# Filters_PWM1kHz.net
KiCad netlist of a schematic drawn in Altium Designer
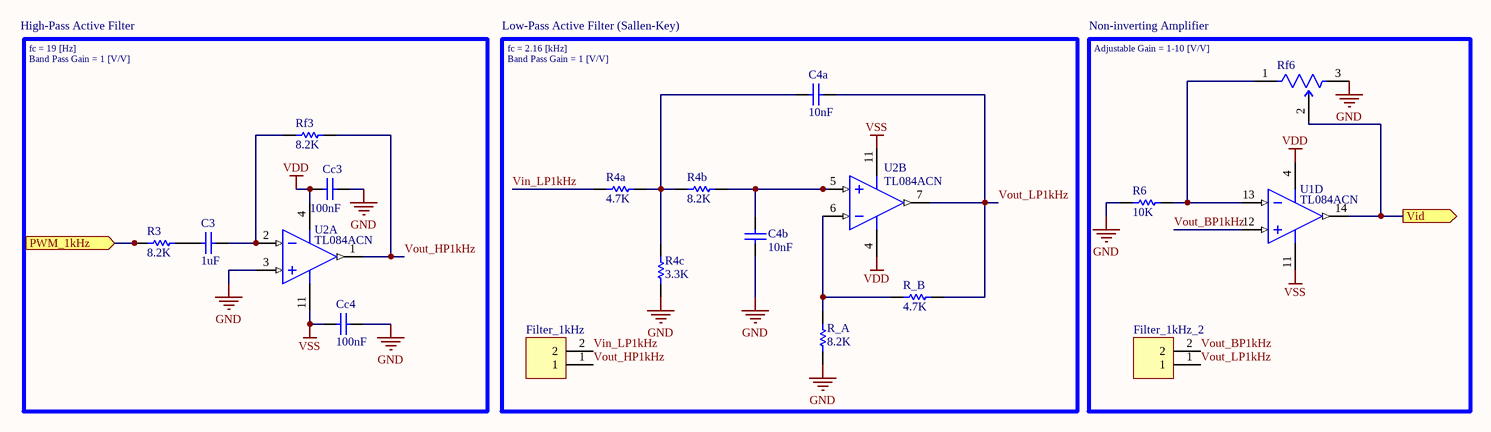
[diagram p0: Filters_PWM1kHz.SchDoc]

(export (version "E")
  (design (tool "Eeschema 10.0.6"))
  (components
    (comp (ref "C3")
      (value "1uF")
      (footprint "condensateur 0.1uf 100mil")
      (description "Capacitor")
      (fields (field (name "Comment") "Cap") (field (name "PUBLISHER") "Altium Limited"))
      (libsource (lib "signal-generator") (part "Cap"))
    )
    (comp (ref "C4a")
      (value "10nF")
      (footprint "condensateur 0.1uf 100mil")
      (description "Capacitor")
      (fields (field (name "Comment") "Cap") (field (name "PUBLISHER") "Altium Limited"))
      (libsource (lib "signal-generator") (part "Cap"))
    )
    (comp (ref "C4b")
      (value "10nF")
      (footprint "condensateur 0.1uf 100mil")
      (description "Capacitor")
      (fields (field (name "Comment") "Cap") (field (name "PUBLISHER") "Altium Limited"))
      (libsource (lib "signal-generator") (part "Cap"))
    )
    (comp (ref "Cc3")
      (value "100nF")
      (footprint "condensateur 0.1uf 100mil")
      (description "Capacitor")
      (fields (field (name "Comment") "Cap") (field (name "PUBLISHER") "Altium Limited"))
      (libsource (lib "signal-generator") (part "Cap"))
    )
    (comp (ref "Cc4")
      (value "100nF")
      (footprint "condensateur 0.1uf 100mil")
      (description "Capacitor")
      (fields (field (name "Comment") "Cap") (field (name "PUBLISHER") "Altium Limited"))
      (libsource (lib "signal-generator") (part "Cap"))
    )
    (comp (ref "Filter_1kHz")
      (value "Jumper")
      (footprint "Header 2P 100mil")
      (description "CONN HEADER VERT 3POS 2.54MM")
      (fields (field (name "PUBLISHER") "Altium Limited"))
      (libsource (lib "PCB_Alimentation_équipe1") (part "header 2 pin_UL"))
    )
    (comp (ref "Filter_1kHz_2")
      (value "Jumper")
      (footprint "Header 2P 100mil")
      (description "CONN HEADER VERT 3POS 2.54MM")
      (fields (field (name "PUBLISHER") "Altium Limited"))
      (libsource (lib "PCB_Alimentation_équipe1") (part "header 2 pin_UL"))
    )
    (comp (ref "R3")
      (value "8.2K")
      (footprint "Resistor_Axial 0.4")
      (description "Resistor")
      (fields (field (name "Comment") "Res1") (field (name "PUBLISHER") "Altium Limited"))
      (libsource (lib "signal-generator") (part "Res1"))
    )
    (comp (ref "R4a")
      (value "4.7K")
      (footprint "Resistor_Axial 0.4")
      (description "Resistor")
      (fields (field (name "Comment") "Res1") (field (name "PUBLISHER") "Altium Limited"))
      (libsource (lib "signal-generator") (part "Res1"))
    )
    (comp (ref "R4b")
      (value "8.2K")
      (footprint "Resistor_Axial 0.4")
      (description "Resistor")
      (fields (field (name "Comment") "Res1") (field (name "PUBLISHER") "Altium Limited"))
      (libsource (lib "signal-generator") (part "Res1"))
    )
    (comp (ref "R4c")
      (value "3.3K")
      (footprint "Resistor_Axial 0.4")
      (description "Resistor")
      (fields (field (name "Comment") "Res1") (field (name "PUBLISHER") "Altium Limited"))
      (libsource (lib "signal-generator") (part "Res1"))
    )
    (comp (ref "R6")
      (value "10K")
      (footprint "Resistor_Axial 0.4")
      (description "Resistor")
      (fields (field (name "Comment") "Res1") (field (name "PUBLISHER") "Altium Limited"))
      (libsource (lib "signal-generator") (part "Res1"))
    )
    (comp (ref "Rf3")
      (value "8.2K")
      (footprint "Resistor_Axial 0.4")
      (description "Resistor")
      (fields (field (name "Comment") "Res1") (field (name "PUBLISHER") "Altium Limited"))
      (libsource (lib "signal-generator") (part "Res1"))
    )
    (comp (ref "Rf6")
      (value "67WR100KLF")
      (footprint "FP-67W-MFG")
      (description "TRIMMER 100K OHM 0.5W PC PIN TOP")
      (fields (field (name "TOLERANCE") "10%"))
      (libsource (lib "Altium Content Vault") (part "a77ee20e32664c43a3a1dd5392b6021"))
    )
    (comp (ref "R_A")
      (value "8.2K")
      (footprint "Resistor_Axial 0.4")
      (description "Resistor")
      (fields (field (name "Comment") "Res1") (field (name "PUBLISHER") "Altium Limited"))
      (libsource (lib "signal-generator") (part "Res1"))
    )
    (comp (ref "R_B")
      (value "4.7K")
      (footprint "Resistor_Axial 0.4")
      (description "Resistor")
      (fields (field (name "Comment") "Res1") (field (name "PUBLISHER") "Altium Limited"))
      (libsource (lib "signal-generator") (part "Res1"))
    )
    (comp (ref "U1")
      (value "TL084ACN")
      (footprint "N0014A")
      (description "JFET-Input Operational Amplifier, 7 to 36 V, 0 to 70 degC, 14-pin DIP (N14), Pb-Free (RoHS)")
      (fields (field (name "MANUFACTURER") "Texas Instruments"))
      (libsource (lib "Altium Content Vault") (part "TI-TLXX4X_MC3403-X14"))
    )
    (comp (ref "U2")
      (value "TL084ACN")
      (footprint "N0014A")
      (description "JFET-Input Operational Amplifier, 7 to 36 V, 0 to 70 degC, 14-pin DIP (N14), Pb-Free (RoHS)")
      (fields (field (name "MANUFACTURER") "Texas Instruments"))
      (libsource (lib "Altium Content Vault") (part "TI-TLXX4X_MC3403-X14"))
    )
  )
  (nets
    (net (code "1") (name "/PWM_1kHz") (class "Default")
      (node (ref "R3") (pin "1") (pinfunction "1_1") (pintype "passive"))
    )
    (net (code "2") (name "/Vid") (class "Default")
      (node (ref "Rf6") (pin "2") (pinfunction "2_2") (pintype "passive"))
      (node (ref "U1") (pin "14") (pinfunction "OUT4_14") (pintype "output"))
    )
    (net (code "3") (name "/Vin_LP1kHz") (class "Default")
      (node (ref "Filter_1kHz") (pin "2") (pinfunction "2_2") (pintype "passive"))
      (node (ref "R4a") (pin "1") (pinfunction "1_1") (pintype "passive"))
    )
    (net (code "4") (name "/Vout_BP1kHz") (class "Default")
      (node (ref "Filter_1kHz_2") (pin "2") (pinfunction "2_2") (pintype "passive"))
      (node (ref "U1") (pin "12") (pinfunction "IN4+_12") (pintype "input"))
    )
    (net (code "5") (name "/Vout_HP1kHz") (class "Default")
      (node (ref "Filter_1kHz") (pin "1") (pinfunction "1_1") (pintype "passive"))
      (node (ref "Rf3") (pin "2") (pinfunction "2_2") (pintype "passive"))
      (node (ref "U2") (pin "1") (pinfunction "OUT1_1") (pintype "output"))
    )
    (net (code "6") (name "/Vout_LP1kHz") (class "Default")
      (node (ref "C4a") (pin "1") (pinfunction "1_1") (pintype "passive"))
      (node (ref "Filter_1kHz_2") (pin "1") (pinfunction "1_1") (pintype "passive"))
      (node (ref "R_B") (pin "2") (pinfunction "2_2") (pintype "passive"))
      (node (ref "U2") (pin "7") (pinfunction "OUT2_7") (pintype "output"))
    )
    (net (code "7") (name "GND") (class "Default")
      (node (ref "C4b") (pin "1") (pinfunction "1_1") (pintype "passive"))
      (node (ref "Cc3") (pin "2") (pinfunction "2_2") (pintype "passive"))
      (node (ref "Cc4") (pin "2") (pinfunction "2_2") (pintype "passive"))
      (node (ref "R4c") (pin "1") (pinfunction "1_1") (pintype "passive"))
      (node (ref "R6") (pin "1") (pinfunction "1_1") (pintype "passive"))
      (node (ref "R_A") (pin "1") (pinfunction "1_1") (pintype "passive"))
      (node (ref "Rf6") (pin "3") (pinfunction "3_3") (pintype "passive"))
      (node (ref "U2") (pin "3") (pinfunction "IN1+_3") (pintype "input"))
    )
    (net (code "8") (name "Net-(C3-Pad1)") (class "Default")
      (node (ref "C3") (pin "1") (pinfunction "1_1") (pintype "passive"))
      (node (ref "R3") (pin "2") (pinfunction "2_2") (pintype "passive"))
    )
    (net (code "9") (name "Net-(C4a-Pad2)") (class "Default")
      (node (ref "C4a") (pin "2") (pinfunction "2_2") (pintype "passive"))
      (node (ref "R4a") (pin "2") (pinfunction "2_2") (pintype "passive"))
      (node (ref "R4b") (pin "1") (pinfunction "1_1") (pintype "passive"))
      (node (ref "R4c") (pin "2") (pinfunction "2_2") (pintype "passive"))
    )
    (net (code "10") (name "Net-(U1D-IN4-)") (class "Default")
      (node (ref "R6") (pin "2") (pinfunction "2_2") (pintype "passive"))
      (node (ref "Rf6") (pin "1") (pinfunction "1_1") (pintype "passive"))
      (node (ref "U1") (pin "13") (pinfunction "IN4-_13") (pintype "input"))
    )
    (net (code "11") (name "Net-(U2A-IN1-)") (class "Default")
      (node (ref "C3") (pin "2") (pinfunction "2_2") (pintype "passive"))
      (node (ref "Rf3") (pin "1") (pinfunction "1_1") (pintype "passive"))
      (node (ref "U2") (pin "2") (pinfunction "IN1-_2") (pintype "input"))
    )
    (net (code "12") (name "Net-(U2B-IN2+)") (class "Default")
      (node (ref "C4b") (pin "2") (pinfunction "2_2") (pintype "passive"))
      (node (ref "R4b") (pin "2") (pinfunction "2_2") (pintype "passive"))
      (node (ref "U2") (pin "5") (pinfunction "IN2+_5") (pintype "input"))
    )
    (net (code "13") (name "Net-(U2B-IN2-)") (class "Default")
      (node (ref "R_A") (pin "2") (pinfunction "2_2") (pintype "passive"))
      (node (ref "R_B") (pin "1") (pinfunction "1_1") (pintype "passive"))
      (node (ref "U2") (pin "6") (pinfunction "IN2-_6") (pintype "input"))
    )
    (net (code "14") (name "VDD") (class "Default")
      (node (ref "Cc3") (pin "1") (pinfunction "1_1") (pintype "passive"))
      (node (ref "U1") (pin "4") (pinfunction "VCC+_4") (pintype "power_in"))
      (node (ref "U2") (pin "4") (pinfunction "VCC+_4") (pintype "power_in"))
    )
    (net (code "15") (name "VSS") (class "Default")
      (node (ref "Cc4") (pin "1") (pinfunction "1_1") (pintype "passive"))
      (node (ref "U1") (pin "11") (pinfunction "VCC-_11") (pintype "power_in"))
      (node (ref "U2") (pin "11") (pinfunction "VCC-_11") (pintype "power_in"))
    )
  )
)
